# rk86_tft.net
KiCad netlist of a schematic drawn in EAGLE
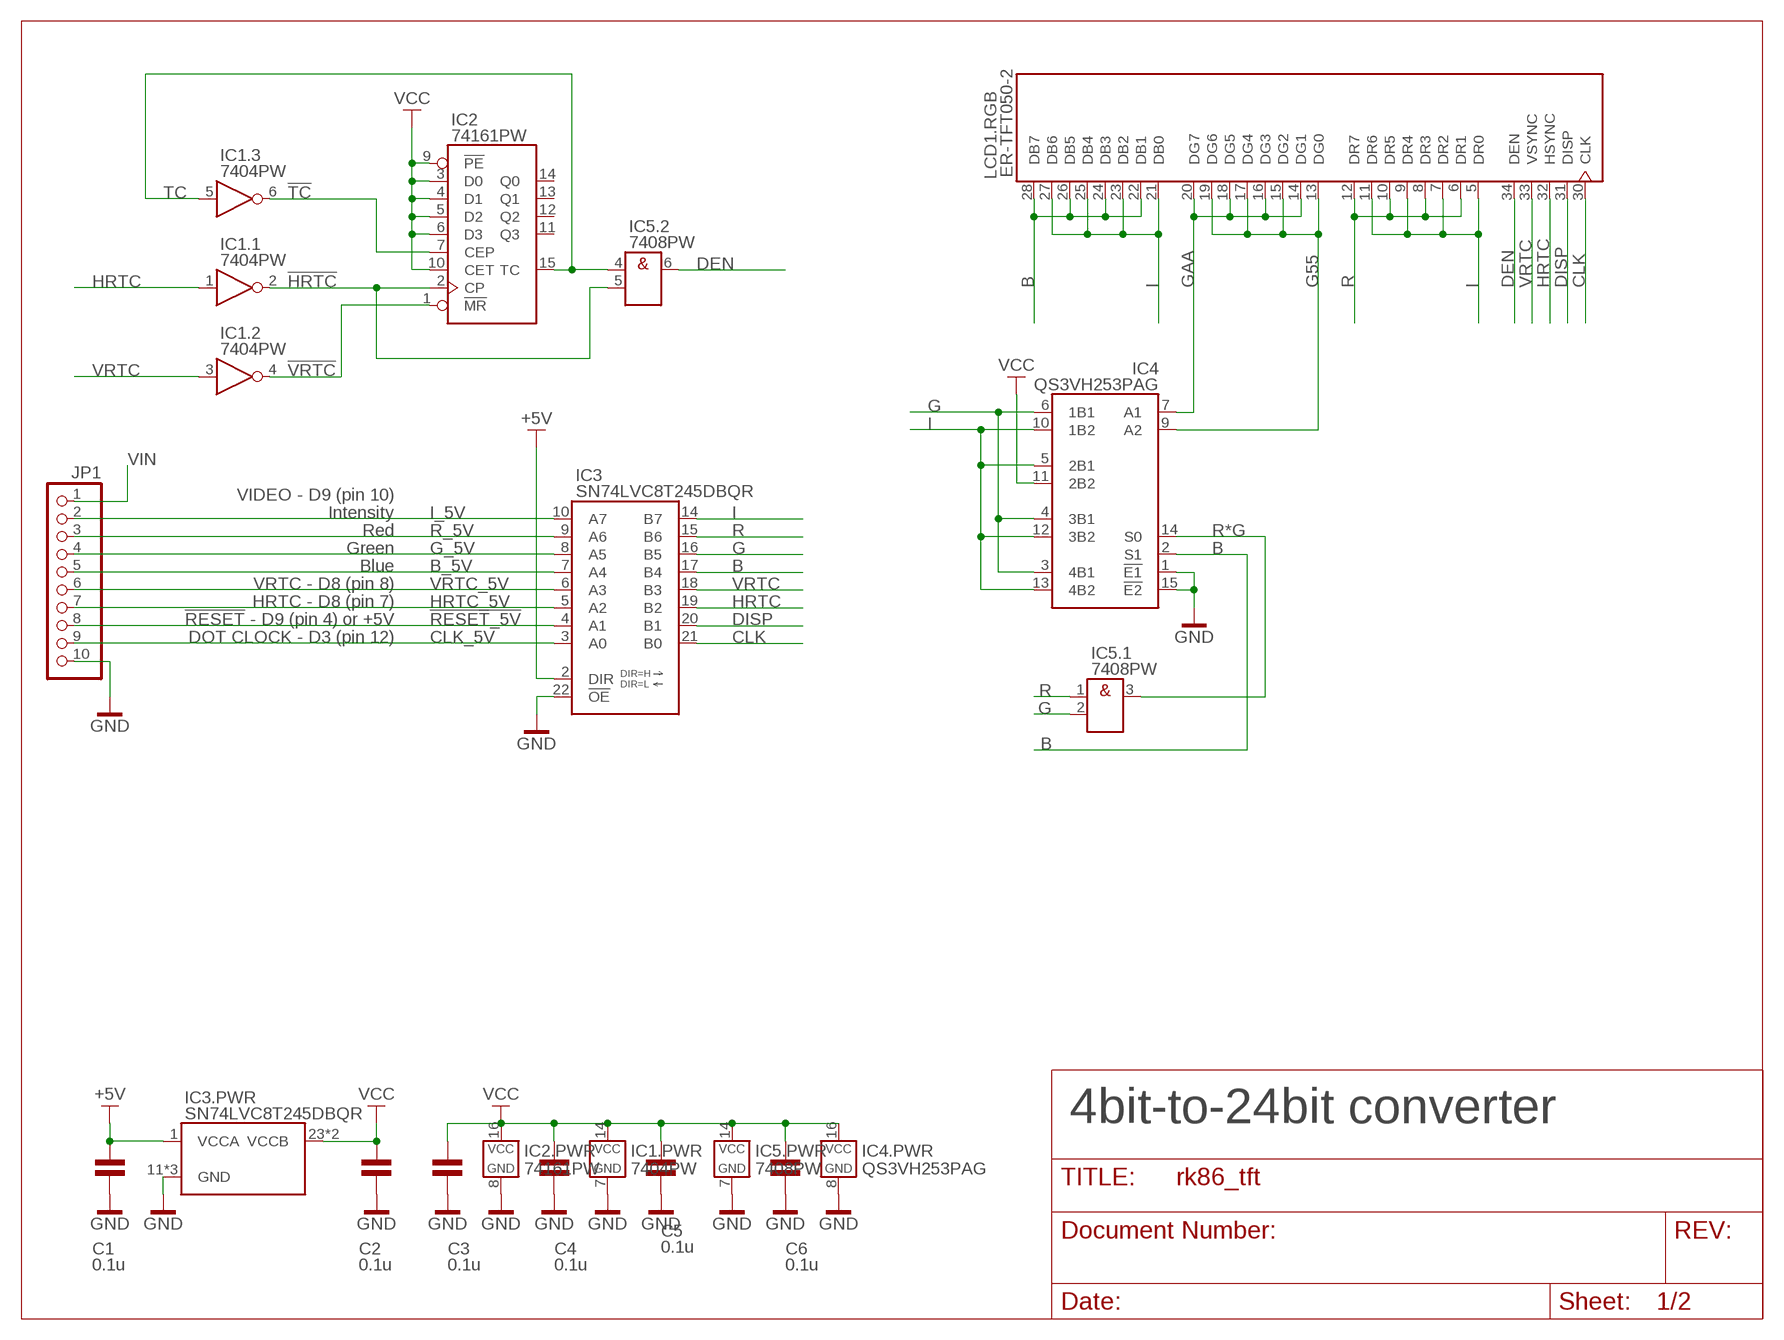
[diagram p0: schematic, sheet 1]
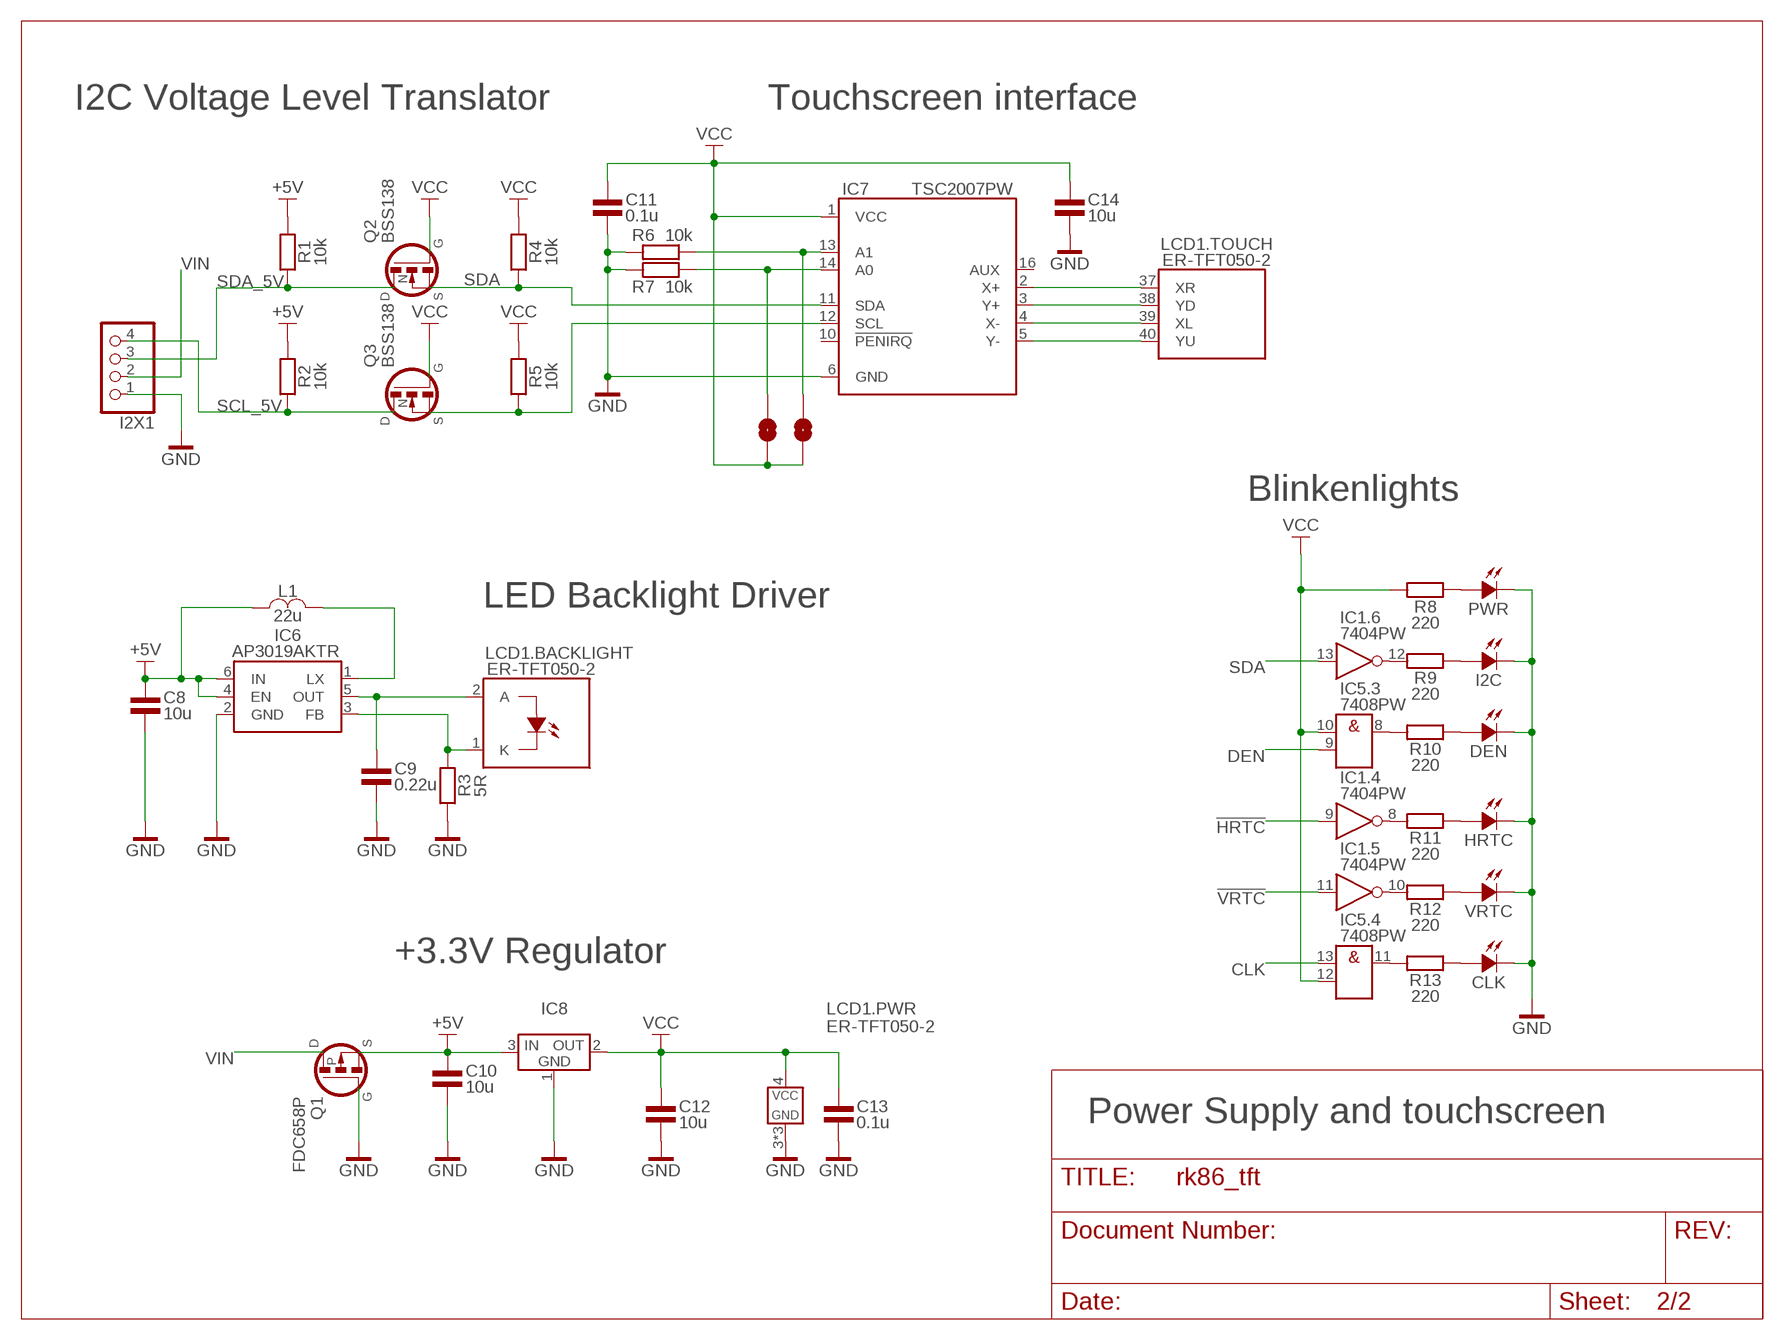
[diagram p1: schematic, sheet 2]

(export (version "E")
  (design (tool "Eeschema 10.0.6"))
  (components
    (comp (ref "A0") (value "SJ") (footprint "eagle-import:SJ") (libsource (lib "eagle-import") (part "SJ")))
    (comp (ref "A1") (value "SJ") (footprint "eagle-import:SJ") (libsource (lib "eagle-import") (part "SJ")))
    (comp (ref "C8")
      (value "10u")
      (footprint "eagle-import:0805")
      (libsource (lib "eagle-import") (part "CAPACITOR_SMD0805"))
    )
    (comp (ref "C9")
      (value "0.22u")
      (footprint "eagle-import:0805")
      (libsource (lib "eagle-import") (part "CAPACITOR_SMD0805"))
    )
    (comp (ref "C10")
      (value "10u")
      (footprint "eagle-import:0805")
      (libsource (lib "eagle-import") (part "CAPACITOR_SMD0805"))
    )
    (comp (ref "C11")
      (value "0.1u")
      (footprint "eagle-import:0805")
      (libsource (lib "eagle-import") (part "CAPACITOR_SMD0805"))
    )
    (comp (ref "C12")
      (value "10u")
      (footprint "eagle-import:0805")
      (libsource (lib "eagle-import") (part "CAPACITOR_SMD0805"))
    )
    (comp (ref "C13")
      (value "0.1u")
      (footprint "eagle-import:0805")
      (libsource (lib "eagle-import") (part "CAPACITOR_SMD0805"))
    )
    (comp (ref "C14")
      (value "10u")
      (footprint "eagle-import:0805")
      (libsource (lib "eagle-import") (part "CAPACITOR_SMD0805"))
    )
    (comp (ref "CLK")
      (value "LED0805")
      (footprint "eagle-import:0805POL")
      (libsource (lib "eagle-import") (part "LED0805"))
    )
    (comp (ref "DEN")
      (value "LED0805")
      (footprint "eagle-import:0805POL")
      (libsource (lib "eagle-import") (part "LED0805"))
    )
    (comp (ref "HRTC")
      (value "LED0805")
      (footprint "eagle-import:0805POL")
      (libsource (lib "eagle-import") (part "LED0805"))
    )
    (comp (ref "I2C")
      (value "LED0805")
      (footprint "eagle-import:0805POL")
      (libsource (lib "eagle-import") (part "LED0805"))
    )
    (comp (ref "I2X1")
      (value "PINHD-1X4/90")
      (footprint "eagle-import:1X04_90")
      (libsource (lib "eagle-import") (part "PINHD-1X4/90"))
    )
    (comp (ref "IC1")
      (value "7404PW")
      (footprint "eagle-import:TSSOP14_4.4")
      (libsource (lib "eagle-import") (part "7404PW"))
    )
    (comp (ref "IC5")
      (value "7408PW")
      (footprint "eagle-import:TSSOP14_4.4")
      (libsource (lib "eagle-import") (part "7408PW"))
    )
    (comp (ref "IC6")
      (value "AP3019AKTR")
      (footprint "eagle-import:SOT23-6")
      (libsource (lib "eagle-import") (part "AP3019AKTR"))
    )
    (comp (ref "IC7")
      (value "TSC2007PW")
      (footprint "eagle-import:TSSOP16_4.4")
      (libsource (lib "eagle-import") (part "TSC2007PW"))
    )
    (comp (ref "IC8")
      (value "MCP1700TT")
      (footprint "eagle-import:SOT23-3")
      (libsource (lib "eagle-import") (part "MCP1700TT"))
    )
    (comp (ref "L1")
      (value "22u")
      (footprint "eagle-import:COILCRAFT_XTL7030")
      (libsource (lib "eagle-import") (part "INDUCTOR_FIXEDXTL7030"))
    )
    (comp (ref "LCD1")
      (value "ER-TFT050-2")
      (footprint "eagle-import:MOLEX_54104-4031")
      (libsource (lib "eagle-import") (part "ER-TFT050-2"))
    )
    (comp (ref "PWR")
      (value "LED0805")
      (footprint "eagle-import:0805POL")
      (libsource (lib "eagle-import") (part "LED0805"))
    )
    (comp (ref "Q1")
      (value "FDC658P")
      (footprint "eagle-import:SOT23-6")
      (libsource (lib "eagle-import") (part "FDC658P"))
    )
    (comp (ref "Q2")
      (value "BSS138")
      (footprint "eagle-import:SOT23-3")
      (libsource (lib "eagle-import") (part "BSS138"))
    )
    (comp (ref "Q3")
      (value "BSS138")
      (footprint "eagle-import:SOT23-3")
      (libsource (lib "eagle-import") (part "BSS138"))
    )
    (comp (ref "R1")
      (value "10k")
      (footprint "eagle-import:0805")
      (libsource (lib "eagle-import") (part "RESISTOR0805"))
    )
    (comp (ref "R2")
      (value "10k")
      (footprint "eagle-import:0805")
      (libsource (lib "eagle-import") (part "RESISTOR0805"))
    )
    (comp (ref "R3")
      (value "5R")
      (footprint "eagle-import:0805")
      (libsource (lib "eagle-import") (part "RESISTOR0805"))
    )
    (comp (ref "R4")
      (value "10k")
      (footprint "eagle-import:0805")
      (libsource (lib "eagle-import") (part "RESISTOR0805"))
    )
    (comp (ref "R5")
      (value "10k")
      (footprint "eagle-import:0805")
      (libsource (lib "eagle-import") (part "RESISTOR0805"))
    )
    (comp (ref "R6")
      (value "10k")
      (footprint "eagle-import:0805")
      (libsource (lib "eagle-import") (part "RESISTOR0805"))
    )
    (comp (ref "R7")
      (value "10k")
      (footprint "eagle-import:0805")
      (libsource (lib "eagle-import") (part "RESISTOR0805"))
    )
    (comp (ref "R8")
      (value "220")
      (footprint "eagle-import:0805")
      (libsource (lib "eagle-import") (part "RESISTOR0805"))
    )
    (comp (ref "R9")
      (value "220")
      (footprint "eagle-import:0805")
      (libsource (lib "eagle-import") (part "RESISTOR0805"))
    )
    (comp (ref "R10")
      (value "220")
      (footprint "eagle-import:0805")
      (libsource (lib "eagle-import") (part "RESISTOR0805"))
    )
    (comp (ref "R11")
      (value "220")
      (footprint "eagle-import:0805")
      (libsource (lib "eagle-import") (part "RESISTOR0805"))
    )
    (comp (ref "R12")
      (value "220")
      (footprint "eagle-import:0805")
      (libsource (lib "eagle-import") (part "RESISTOR0805"))
    )
    (comp (ref "R13")
      (value "220")
      (footprint "eagle-import:0805")
      (libsource (lib "eagle-import") (part "RESISTOR0805"))
    )
    (comp (ref "VRTC")
      (value "LED0805")
      (footprint "eagle-import:0805POL")
      (libsource (lib "eagle-import") (part "LED0805"))
    )
    (comp (ref "C1")
      (value "0.1u")
      (footprint "eagle-import:0805")
      (libsource (lib "eagle-import") (part "CAPACITOR_SMD0805"))
    )
    (comp (ref "C2")
      (value "0.1u")
      (footprint "eagle-import:0805")
      (libsource (lib "eagle-import") (part "CAPACITOR_SMD0805"))
    )
    (comp (ref "C3")
      (value "0.1u")
      (footprint "eagle-import:0805")
      (libsource (lib "eagle-import") (part "CAPACITOR_SMD0805"))
    )
    (comp (ref "C4")
      (value "0.1u")
      (footprint "eagle-import:0805")
      (libsource (lib "eagle-import") (part "CAPACITOR_SMD0805"))
    )
    (comp (ref "C5")
      (value "0.1u")
      (footprint "eagle-import:0805")
      (libsource (lib "eagle-import") (part "CAPACITOR_SMD0805"))
    )
    (comp (ref "C6")
      (value "0.1u")
      (footprint "eagle-import:0805")
      (libsource (lib "eagle-import") (part "CAPACITOR_SMD0805"))
    )
    (comp (ref "IC2")
      (value "74161PW")
      (footprint "eagle-import:TSSOP16_4.4")
      (libsource (lib "eagle-import") (part "74161PW"))
    )
    (comp (ref "IC3")
      (value "SN74LVC8T245DBQR")
      (footprint "eagle-import:TI_DBQ24")
      (libsource (lib "eagle-import") (part "SN74LVC8T245DBQR"))
    )
    (comp (ref "IC4")
      (value "QS3VH253PAG")
      (footprint "eagle-import:TSSOP16_4.4")
      (libsource (lib "eagle-import") (part "QS3VH253PAG"))
    )
    (comp (ref "JP1")
      (value "PINHD-1X10/90")
      (footprint "eagle-import:1X10_90")
      (libsource (lib "eagle-import") (part "PINHD-1X10/90"))
    )
  )
  (nets
    (net (code "1") (name "+5V") (class "Default")
      (node (ref "C1") (pin "2") (pinfunction "P$2_2") (pintype "passive"))
      (node (ref "C10") (pin "2") (pinfunction "P$2_2") (pintype "passive"))
      (node (ref "C8") (pin "2") (pinfunction "P$2_2") (pintype "passive"))
      (node (ref "IC3") (pin "1") (pinfunction "VCCA_1") (pintype "power_in"))
      (node (ref "IC3") (pin "2") (pinfunction "DIR_2") (pintype "input"))
      (node (ref "IC6") (pin "4") (pinfunction "EN_4") (pintype "input"))
      (node (ref "IC6") (pin "6") (pinfunction "IN_6") (pintype "input"))
      (node (ref "IC8") (pin "3") (pinfunction "IN_3") (pintype "input"))
      (node (ref "L1") (pin "1") (pinfunction "P$1_1") (pintype "passive"))
      (node (ref "Q1") (pin "4") (pinfunction "S_4") (pintype "passive"))
      (node (ref "R1") (pin "2") (pinfunction "P$2_2") (pintype "passive"))
      (node (ref "R2") (pin "2") (pinfunction "P$2_2") (pintype "passive"))
    )
    (net (code "2") (name "B") (class "Default")
      (node (ref "IC3") (pin "17") (pinfunction "B4_17") (pintype "bidirectional"))
      (node (ref "IC4") (pin "2") (pinfunction "S1_2") (pintype "input"))
      (node (ref "LCD1") (pin "22") (pinfunction "DB1_22") (pintype "input"))
      (node (ref "LCD1") (pin "24") (pinfunction "DB3_24") (pintype "input"))
      (node (ref "LCD1") (pin "26") (pinfunction "DB5_26") (pintype "input"))
      (node (ref "LCD1") (pin "28") (pinfunction "DB7_28") (pintype "input"))
    )
    (net (code "3") (name "B_5V") (class "Default")
      (node (ref "IC3") (pin "7") (pinfunction "A4_7") (pintype "bidirectional"))
      (node (ref "JP1") (pin "5") (pinfunction "5_5") (pintype "passive"))
    )
    (net (code "4") (name "CLK") (class "Default")
      (node (ref "IC3") (pin "21") (pinfunction "B0_21") (pintype "bidirectional"))
      (node (ref "IC5") (pin "13") (pinfunction "A_13") (pintype "input"))
      (node (ref "LCD1") (pin "30") (pinfunction "CLK_30") (pintype "input"))
    )
    (net (code "5") (name "CLK_5V") (class "Default")
      (node (ref "IC3") (pin "3") (pinfunction "A0_3") (pintype "bidirectional"))
      (node (ref "JP1") (pin "9") (pinfunction "9_9") (pintype "passive"))
    )
    (net (code "6") (name "DEN") (class "Default")
      (node (ref "IC5") (pin "6") (pinfunction "Y_6") (pintype "output"))
      (node (ref "IC5") (pin "9") (pinfunction "B_9") (pintype "input"))
      (node (ref "LCD1") (pin "34") (pinfunction "DEN_34") (pintype "input"))
    )
    (net (code "7") (name "DISP") (class "Default")
      (node (ref "IC3") (pin "20") (pinfunction "B1_20") (pintype "bidirectional"))
      (node (ref "LCD1") (pin "31") (pinfunction "DISP_31") (pintype "input"))
    )
    (net (code "8") (name "G") (class "Default")
      (node (ref "IC3") (pin "16") (pinfunction "B5_16") (pintype "bidirectional"))
      (node (ref "IC4") (pin "3") (pinfunction "4B1_3") (pintype "passive"))
      (node (ref "IC4") (pin "4") (pinfunction "3B1_4") (pintype "passive"))
      (node (ref "IC4") (pin "6") (pinfunction "1B1_6") (pintype "passive"))
      (node (ref "IC5") (pin "2") (pinfunction "B_2") (pintype "input"))
    )
    (net (code "9") (name "G55") (class "Default")
      (node (ref "IC4") (pin "9") (pinfunction "A2_9") (pintype "passive"))
      (node (ref "LCD1") (pin "13") (pinfunction "DG0_13") (pintype "input"))
      (node (ref "LCD1") (pin "15") (pinfunction "DG2_15") (pintype "input"))
      (node (ref "LCD1") (pin "17") (pinfunction "DG4_17") (pintype "input"))
      (node (ref "LCD1") (pin "19") (pinfunction "DG6_19") (pintype "input"))
    )
    (net (code "10") (name "GAA") (class "Default")
      (node (ref "IC4") (pin "7") (pinfunction "A1_7") (pintype "passive"))
      (node (ref "LCD1") (pin "14") (pinfunction "DG1_14") (pintype "input"))
      (node (ref "LCD1") (pin "16") (pinfunction "DG3_16") (pintype "input"))
      (node (ref "LCD1") (pin "18") (pinfunction "DG5_18") (pintype "input"))
      (node (ref "LCD1") (pin "20") (pinfunction "DG7_20") (pintype "input"))
    )
    (net (code "11") (name "GND") (class "Default")
      (node (ref "C1") (pin "1") (pinfunction "P$1_1") (pintype "passive"))
      (node (ref "C10") (pin "1") (pinfunction "P$1_1") (pintype "passive"))
      (node (ref "C11") (pin "1") (pinfunction "P$1_1") (pintype "passive"))
      (node (ref "C12") (pin "1") (pinfunction "P$1_1") (pintype "passive"))
      (node (ref "C13") (pin "1") (pinfunction "P$1_1") (pintype "passive"))
      (node (ref "C14") (pin "1") (pinfunction "P$1_1") (pintype "passive"))
      (node (ref "C2") (pin "1") (pinfunction "P$1_1") (pintype "passive"))
      (node (ref "C3") (pin "1") (pinfunction "P$1_1") (pintype "passive"))
      (node (ref "C4") (pin "1") (pinfunction "P$1_1") (pintype "passive"))
      (node (ref "C5") (pin "1") (pinfunction "P$1_1") (pintype "passive"))
      (node (ref "C6") (pin "1") (pinfunction "P$1_1") (pintype "passive"))
      (node (ref "C8") (pin "1") (pinfunction "P$1_1") (pintype "passive"))
      (node (ref "C9") (pin "1") (pinfunction "P$1_1") (pintype "passive"))
      (node (ref "CLK") (pin "K") (pinfunction "K_K") (pintype "passive"))
      (node (ref "DEN") (pin "K") (pinfunction "K_K") (pintype "passive"))
      (node (ref "HRTC") (pin "K") (pinfunction "K_K") (pintype "passive"))
      (node (ref "I2C") (pin "K") (pinfunction "K_K") (pintype "passive"))
      (node (ref "I2X1") (pin "1") (pinfunction "1_1") (pintype "passive"))
      (node (ref "IC1") (pin "7") (pinfunction "GND_7") (pintype "power_in"))
      (node (ref "IC2") (pin "8") (pinfunction "GND_8") (pintype "power_in"))
      (node (ref "IC3") (pin "11") (pinfunction "GND_11") (pintype "power_in"))
      (node (ref "IC3") (pin "12") (pinfunction "GND_12") (pintype "power_in"))
      (node (ref "IC3") (pin "13") (pinfunction "GND_13") (pintype "power_in"))
      (node (ref "IC3") (pin "22") (pinfunction "~{OE}_22") (pintype "input"))
      (node (ref "IC4") (pin "1") (pinfunction "~{E1}_1") (pintype "input"))
      (node (ref "IC4") (pin "15") (pinfunction "~{E2}_15") (pintype "input"))
      (node (ref "IC4") (pin "8") (pinfunction "GND_8") (pintype "power_in"))
      (node (ref "IC5") (pin "7") (pinfunction "GND_7") (pintype "power_in"))
      (node (ref "IC6") (pin "2") (pinfunction "GND_2") (pintype "power_in"))
      (node (ref "IC7") (pin "6") (pinfunction "GND_6") (pintype "power_in"))
      (node (ref "IC8") (pin "1") (pinfunction "GND_1") (pintype "power_in"))
      (node (ref "JP1") (pin "10") (pinfunction "10_10") (pintype "passive"))
      (node (ref "LCD1") (pin "29") (pinfunction "GND_29") (pintype "power_in"))
      (node (ref "LCD1") (pin "3") (pinfunction "GND_3") (pintype "power_in"))
      (node (ref "LCD1") (pin "36") (pinfunction "GND_36") (pintype "power_in"))
      (node (ref "PWR") (pin "K") (pinfunction "K_K") (pintype "passive"))
      (node (ref "Q1") (pin "3") (pinfunction "G_3") (pintype "passive"))
      (node (ref "R3") (pin "1") (pinfunction "P$1_1") (pintype "passive"))
      (node (ref "R6") (pin "1") (pinfunction "P$1_1") (pintype "passive"))
      (node (ref "R7") (pin "1") (pinfunction "P$1_1") (pintype "passive"))
      (node (ref "VRTC") (pin "K") (pinfunction "K_K") (pintype "passive"))
    )
    (net (code "12") (name "G_5V") (class "Default")
      (node (ref "IC3") (pin "8") (pinfunction "A5_8") (pintype "bidirectional"))
      (node (ref "JP1") (pin "4") (pinfunction "4_4") (pintype "passive"))
    )
    (net (code "13") (name "HRTC") (class "Default")
      (node (ref "IC1") (pin "1") (pinfunction "A_1") (pintype "input"))
      (node (ref "IC3") (pin "19") (pinfunction "B2_19") (pintype "bidirectional"))
      (node (ref "LCD1") (pin "32") (pinfunction "HSYNC_32") (pintype "input"))
    )
    (net (code "14") (name "HRTC_5V") (class "Default")
      (node (ref "IC3") (pin "5") (pinfunction "A2_5") (pintype "bidirectional"))
      (node (ref "JP1") (pin "7") (pinfunction "7_7") (pintype "passive"))
    )
    (net (code "15") (name "I") (class "Default")
      (node (ref "IC3") (pin "14") (pinfunction "B7_14") (pintype "bidirectional"))
      (node (ref "IC4") (pin "10") (pinfunction "1B2_10") (pintype "passive"))
      (node (ref "IC4") (pin "12") (pinfunction "3B2_12") (pintype "passive"))
      (node (ref "IC4") (pin "13") (pinfunction "4B2_13") (pintype "passive"))
      (node (ref "IC4") (pin "5") (pinfunction "2B1_5") (pintype "passive"))
      (node (ref "LCD1") (pin "11") (pinfunction "DR6_11") (pintype "input"))
      (node (ref "LCD1") (pin "21") (pinfunction "DB0_21") (pintype "input"))
      (node (ref "LCD1") (pin "23") (pinfunction "DB2_23") (pintype "input"))
      (node (ref "LCD1") (pin "25") (pinfunction "DB4_25") (pintype "input"))
      (node (ref "LCD1") (pin "27") (pinfunction "DB6_27") (pintype "input"))
      (node (ref "LCD1") (pin "5") (pinfunction "DR0_5") (pintype "input"))
      (node (ref "LCD1") (pin "7") (pinfunction "DR2_7") (pintype "input"))
      (node (ref "LCD1") (pin "9") (pinfunction "DR4_9") (pintype "input"))
    )
    (net (code "16") (name "I_5V") (class "Default")
      (node (ref "IC3") (pin "10") (pinfunction "A7_10") (pintype "bidirectional"))
      (node (ref "JP1") (pin "2") (pinfunction "2_2") (pintype "passive"))
    )
    (net (code "17") (name "Net-(C9-P$2)") (class "Default")
      (node (ref "C9") (pin "2") (pinfunction "P$2_2") (pintype "passive"))
      (node (ref "IC6") (pin "5") (pinfunction "OUT_5") (pintype "passive"))
      (node (ref "LCD1") (pin "2") (pinfunction "A_2") (pintype "passive"))
    )
    (net (code "18") (name "Net-(IC1D-Y)") (class "Default")
      (node (ref "IC1") (pin "8") (pinfunction "Y_8") (pintype "output"))
      (node (ref "R11") (pin "1") (pinfunction "P$1_1") (pintype "passive"))
    )
    (net (code "19") (name "Net-(IC1E-Y)") (class "Default")
      (node (ref "IC1") (pin "10") (pinfunction "Y_10") (pintype "output"))
      (node (ref "R12") (pin "1") (pinfunction "P$1_1") (pintype "passive"))
    )
    (net (code "20") (name "Net-(IC1F-Y)") (class "Default")
      (node (ref "IC1") (pin "12") (pinfunction "Y_12") (pintype "output"))
      (node (ref "R9") (pin "1") (pinfunction "P$1_1") (pintype "passive"))
    )
    (net (code "21") (name "Net-(IC5C-Y)") (class "Default")
      (node (ref "IC5") (pin "8") (pinfunction "Y_8") (pintype "output"))
      (node (ref "R10") (pin "1") (pinfunction "P$1_1") (pintype "passive"))
    )
    (net (code "22") (name "Net-(IC5D-Y)") (class "Default")
      (node (ref "IC5") (pin "11") (pinfunction "Y_11") (pintype "output"))
      (node (ref "R13") (pin "1") (pinfunction "P$1_1") (pintype "passive"))
    )
    (net (code "23") (name "Net-(IC6-FB)") (class "Default")
      (node (ref "IC6") (pin "3") (pinfunction "FB_3") (pintype "input"))
      (node (ref "LCD1") (pin "1") (pinfunction "K_1") (pintype "passive"))
      (node (ref "R3") (pin "2") (pinfunction "P$2_2") (pintype "passive"))
    )
    (net (code "24") (name "Net-(IC6-LX)") (class "Default")
      (node (ref "IC6") (pin "1") (pinfunction "LX_1") (pintype "passive"))
      (node (ref "L1") (pin "2") (pinfunction "P$2_2") (pintype "passive"))
    )
    (net (code "25") (name "Net-(IC7-A0)") (class "Default")
      (node (ref "A0") (pin "2") (pinfunction "2_2") (pintype "passive"))
      (node (ref "IC7") (pin "14") (pinfunction "A0_14") (pintype "bidirectional"))
      (node (ref "R7") (pin "2") (pinfunction "P$2_2") (pintype "passive"))
    )
    (net (code "26") (name "Net-(IC7-A1)") (class "Default")
      (node (ref "A1") (pin "2") (pinfunction "2_2") (pintype "passive"))
      (node (ref "IC7") (pin "13") (pinfunction "A1_13") (pintype "input"))
      (node (ref "R6") (pin "2") (pinfunction "P$2_2") (pintype "passive"))
    )
    (net (code "27") (name "Net-(IC7-SCL)") (class "Default")
      (node (ref "IC7") (pin "12") (pinfunction "SCL_12") (pintype "input"))
      (node (ref "Q3") (pin "2") (pinfunction "S_2") (pintype "passive"))
      (node (ref "R5") (pin "1") (pinfunction "P$1_1") (pintype "passive"))
    )
    (net (code "28") (name "Net-(IC7-X+)") (class "Default")
      (node (ref "IC7") (pin "2") (pinfunction "X+_2") (pintype "bidirectional"))
      (node (ref "LCD1") (pin "37") (pinfunction "XR_37") (pintype "passive"))
    )
    (net (code "29") (name "Net-(IC7-X-)") (class "Default")
      (node (ref "IC7") (pin "4") (pinfunction "X-_4") (pintype "bidirectional"))
      (node (ref "LCD1") (pin "39") (pinfunction "XL_39") (pintype "passive"))
    )
    (net (code "30") (name "Net-(IC7-Y+)") (class "Default")
      (node (ref "IC7") (pin "3") (pinfunction "Y+_3") (pintype "bidirectional"))
      (node (ref "LCD1") (pin "38") (pinfunction "YD_38") (pintype "passive"))
    )
    (net (code "31") (name "Net-(IC7-Y-)") (class "Default")
      (node (ref "IC7") (pin "5") (pinfunction "Y-_5") (pintype "bidirectional"))
      (node (ref "LCD1") (pin "40") (pinfunction "YU_40") (pintype "passive"))
    )
    (net (code "32") (name "Net-(R8-P$2)") (class "Default")
      (node (ref "PWR") (pin "A") (pinfunction "A_A") (pintype "passive"))
      (node (ref "R8") (pin "2") (pinfunction "P$2_2") (pintype "passive"))
    )
    (net (code "33") (name "Net-(R9-P$2)") (class "Default")
      (node (ref "I2C") (pin "A") (pinfunction "A_A") (pintype "passive"))
      (node (ref "R9") (pin "2") (pinfunction "P$2_2") (pintype "passive"))
    )
    (net (code "34") (name "Net-(R10-P$2)") (class "Default")
      (node (ref "DEN") (pin "A") (pinfunction "A_A") (pintype "passive"))
      (node (ref "R10") (pin "2") (pinfunction "P$2_2") (pintype "passive"))
    )
    (net (code "35") (name "Net-(R11-P$2)") (class "Default")
      (node (ref "HRTC") (pin "A") (pinfunction "A_A") (pintype "passive"))
      (node (ref "R11") (pin "2") (pinfunction "P$2_2") (pintype "passive"))
    )
    (net (code "36") (name "Net-(R12-P$2)") (class "Default")
      (node (ref "R12") (pin "2") (pinfunction "P$2_2") (pintype "passive"))
      (node (ref "VRTC") (pin "A") (pinfunction "A_A") (pintype "passive"))
    )
    (net (code "37") (name "Net-(R13-P$2)") (class "Default")
      (node (ref "CLK") (pin "A") (pinfunction "A_A") (pintype "passive"))
      (node (ref "R13") (pin "2") (pinfunction "P$2_2") (pintype "passive"))
    )
    (net (code "38") (name "R") (class "Default")
      (node (ref "IC3") (pin "15") (pinfunction "B6_15") (pintype "bidirectional"))
      (node (ref "IC5") (pin "1") (pinfunction "A_1") (pintype "input"))
      (node (ref "LCD1") (pin "10") (pinfunction "DR5_10") (pintype "input"))
      (node (ref "LCD1") (pin "12") (pinfunction "DR7_12") (pintype "input"))
      (node (ref "LCD1") (pin "6") (pinfunction "DR1_6") (pintype "input"))
      (node (ref "LCD1") (pin "8") (pinfunction "DR3_8") (pintype "input"))
    )
    (net (code "39") (name "R*G") (class "Default")
      (node (ref "IC4") (pin "14") (pinfunction "S0_14") (pintype "input"))
      (node (ref "IC5") (pin "3") (pinfunction "Y_3") (pintype "output"))
    )
    (net (code "40") (name "R_5V") (class "Default")
      (node (ref "IC3") (pin "9") (pinfunction "A6_9") (pintype "bidirectional"))
      (node (ref "JP1") (pin "3") (pinfunction "3_3") (pintype "passive"))
    )
    (net (code "41") (name "SCL_5V") (class "Default")
      (node (ref "I2X1") (pin "4") (pinfunction "4_4") (pintype "passive"))
      (node (ref "Q3") (pin "3") (pinfunction "D_3") (pintype "passive"))
      (node (ref "R2") (pin "1") (pinfunction "P$1_1") (pintype "passive"))
    )
    (net (code "42") (name "SDA") (class "Default")
      (node (ref "IC1") (pin "13") (pinfunction "A_13") (pintype "input"))
      (node (ref "IC7") (pin "11") (pinfunction "SDA_11") (pintype "bidirectional"))
      (node (ref "Q2") (pin "2") (pinfunction "S_2") (pintype "passive"))
      (node (ref "R4") (pin "1") (pinfunction "P$1_1") (pintype "passive"))
    )
    (net (code "43") (name "SDA_5V") (class "Default")
      (node (ref "I2X1") (pin "3") (pinfunction "3_3") (pintype "passive"))
      (node (ref "Q2") (pin "3") (pinfunction "D_3") (pintype "passive"))
      (node (ref "R1") (pin "1") (pinfunction "P$1_1") (pintype "passive"))
    )
    (net (code "44") (name "TC") (class "Default")
      (node (ref "IC1") (pin "5") (pinfunction "A_5") (pintype "input"))
      (node (ref "IC2") (pin "15") (pinfunction "TC_15") (pintype "output"))
      (node (ref "IC5") (pin "4") (pinfunction "A_4") (pintype "input"))
    )
    (net (code "45") (name "VCC") (class "Default")
      (node (ref "A0") (pin "1") (pinfunction "1_1") (pintype "passive"))
      (node (ref "A1") (pin "1") (pinfunction "1_1") (pintype "passive"))
      (node (ref "C11") (pin "2") (pinfunction "P$2_2") (pintype "passive"))
      (node (ref "C12") (pin "2") (pinfunction "P$2_2") (pintype "passive"))
      (node (ref "C13") (pin "2") (pinfunction "P$2_2") (pintype "passive"))
      (node (ref "C14") (pin "2") (pinfunction "P$2_2") (pintype "passive"))
      (node (ref "C2") (pin "2") (pinfunction "P$2_2") (pintype "passive"))
      (node (ref "C3") (pin "2") (pinfunction "P$2_2") (pintype "passive"))
      (node (ref "C4") (pin "2") (pinfunction "P$2_2") (pintype "passive"))
      (node (ref "C5") (pin "2") (pinfunction "P$2_2") (pintype "passive"))
      (node (ref "C6") (pin "2") (pinfunction "P$2_2") (pintype "passive"))
      (node (ref "IC1") (pin "14") (pinfunction "VCC_14") (pintype "power_in"))
      (node (ref "IC2") (pin "10") (pinfunction "CET_10") (pintype "input"))
      (node (ref "IC2") (pin "16") (pinfunction "VCC_16") (pintype "power_in"))
      (node (ref "IC2") (pin "3") (pinfunction "D0_3") (pintype "input"))
      (node (ref "IC2") (pin "4") (pinfunction "D1_4") (pintype "input"))
      (node (ref "IC2") (pin "5") (pinfunction "D2_5") (pintype "input"))
      (node (ref "IC2") (pin "6") (pinfunction "D3_6") (pintype "input"))
      (node (ref "IC2") (pin "9") (pinfunction "~{PE}_9") (pintype "input"))
      (node (ref "IC3") (pin "23") (pinfunction "VCCB_23") (pintype "power_in"))
      (node (ref "IC3") (pin "24") (pinfunction "VCCB_24") (pintype "power_in"))
      (node (ref "IC4") (pin "11") (pinfunction "2B2_11") (pintype "passive"))
      (node (ref "IC4") (pin "16") (pinfunction "VCC_16") (pintype "power_in"))
      (node (ref "IC5") (pin "10") (pinfunction "A_10") (pintype "input"))
      (node (ref "IC5") (pin "12") (pinfunction "B_12") (pintype "input"))
      (node (ref "IC5") (pin "14") (pinfunction "VCC_14") (pintype "power_in"))
      (node (ref "IC7") (pin "1") (pinfunction "VCC_1") (pintype "power_in"))
      (node (ref "IC8") (pin "2") (pinfunction "OUT_2") (pintype "passive"))
      (node (ref "LCD1") (pin "4") (pinfunction "VCC_4") (pintype "power_in"))
      (node (ref "Q2") (pin "1") (pinfunction "G_1") (pintype "passive"))
      (node (ref "Q3") (pin "1") (pinfunction "G_1") (pintype "passive"))
      (node (ref "R4") (pin "2") (pinfunction "P$2_2") (pintype "passive"))
      (node (ref "R5") (pin "2") (pinfunction "P$2_2") (pintype "passive"))
      (node (ref "R8") (pin "1") (pinfunction "P$1_1") (pintype "passive"))
    )
    (net (code "46") (name "VIN") (class "Default")
      (node (ref "I2X1") (pin "2") (pinfunction "2_2") (pintype "passive"))
      (node (ref "JP1") (pin "1") (pinfunction "1_1") (pintype "passive"))
      (node (ref "Q1") (pin "1") (pinfunction "D_1") (pintype "passive"))
      (node (ref "Q1") (pin "2") (pinfunction "D_2") (pintype "passive"))
      (node (ref "Q1") (pin "5") (pinfunction "D_5") (pintype "passive"))
      (node (ref "Q1") (pin "6") (pinfunction "D_6") (pintype "passive"))
    )
    (net (code "47") (name "VRTC") (class "Default")
      (node (ref "IC1") (pin "3") (pinfunction "A_3") (pintype "input"))
      (node (ref "IC3") (pin "18") (pinfunction "B3_18") (pintype "bidirectional"))
      (node (ref "LCD1") (pin "33") (pinfunction "VSYNC_33") (pintype "input"))
    )
    (net (code "48") (name "VRTC_5V") (class "Default")
      (node (ref "IC3") (pin "6") (pinfunction "A3_6") (pintype "bidirectional"))
      (node (ref "JP1") (pin "6") (pinfunction "6_6") (pintype "passive"))
    )
    (net (code "49") (name "unconnected-(IC2A-Q0-Pad14)") (class "Default")
      (node (ref "IC2") (pin "14") (pinfunction "Q0_14") (pintype "output"))
    )
    (net (code "50") (name "unconnected-(IC2A-Q1-Pad13)") (class "Default")
      (node (ref "IC2") (pin "13") (pinfunction "Q1_13") (pintype "output"))
    )
    (net (code "51") (name "unconnected-(IC2A-Q2-Pad12)") (class "Default")
      (node (ref "IC2") (pin "12") (pinfunction "Q2_12") (pintype "output"))
    )
    (net (code "52") (name "unconnected-(IC2A-Q3-Pad11)") (class "Default")
      (node (ref "IC2") (pin "11") (pinfunction "Q3_11") (pintype "output"))
    )
    (net (code "53") (name "unconnected-(IC7-AUX-Pad16)") (class "Default")
      (node (ref "IC7") (pin "16") (pinfunction "AUX_16") (pintype "bidirectional"))
    )
    (net (code "54") (name "unconnected-(IC7-~{PENIRQ}-Pad10)") (class "Default")
      (node (ref "IC7") (pin "10") (pinfunction "~{PENIRQ}_10") (pintype "output"))
    )
    (net (code "55") (name "~{HRTC}") (class "Default")
      (node (ref "IC1") (pin "2") (pinfunction "Y_2") (pintype "output"))
      (node (ref "IC1") (pin "9") (pinfunction "A_9") (pintype "input"))
      (node (ref "IC2") (pin "2") (pinfunction "CP_2") (pintype "input"))
      (node (ref "IC5") (pin "5") (pinfunction "B_5") (pintype "input"))
    )
    (net (code "56") (name "~{RESET_5V}") (class "Default")
      (node (ref "IC3") (pin "4") (pinfunction "A1_4") (pintype "bidirectional"))
      (node (ref "JP1") (pin "8") (pinfunction "8_8") (pintype "passive"))
    )
    (net (code "57") (name "~{TC}") (class "Default")
      (node (ref "IC1") (pin "6") (pinfunction "Y_6") (pintype "output"))
      (node (ref "IC2") (pin "7") (pinfunction "CEP_7") (pintype "input"))
    )
    (net (code "58") (name "~{VRTC}") (class "Default")
      (node (ref "IC1") (pin "11") (pinfunction "A_11") (pintype "input"))
      (node (ref "IC1") (pin "4") (pinfunction "Y_4") (pintype "output"))
      (node (ref "IC2") (pin "1") (pinfunction "~{MR}_1") (pintype "input"))
    )
  )
)
